# Sheet1.net
KiCad netlist of a schematic drawn in Altium Designer
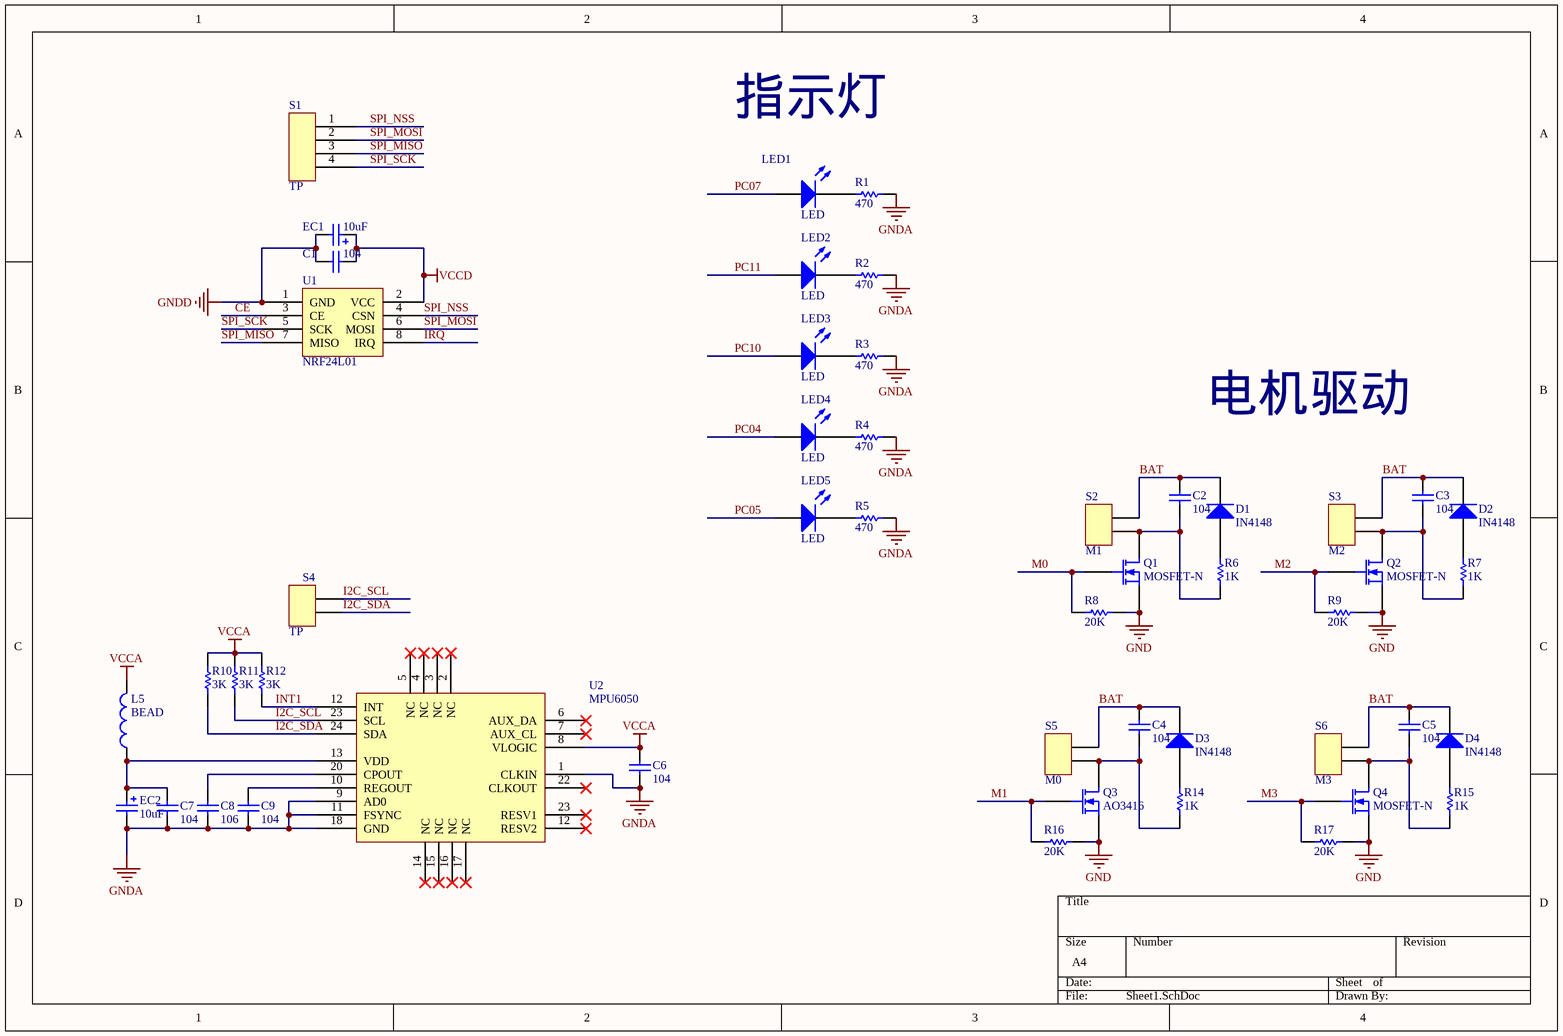
[diagram p0: Sheet1.SchDoc]

(export (version "E")
  (design (tool "Eeschema 10.0.6"))
  (components
    (comp (ref "C1") (value "104") (footprint "0603") (libsource (lib "yezi_sch") (part "CAP")))
    (comp (ref "C2") (value "104") (footprint "0603") (libsource (lib "yezi_sch") (part "CAP")))
    (comp (ref "C3") (value "104") (footprint "0603") (libsource (lib "yezi_sch") (part "CAP")))
    (comp (ref "C4") (value "104") (footprint "0603") (libsource (lib "yezi_sch") (part "CAP")))
    (comp (ref "C5") (value "104") (footprint "0603") (libsource (lib "yezi_sch") (part "CAP")))
    (comp (ref "C6") (value "104") (footprint "0603") (libsource (lib "yezi_sch") (part "CAP")))
    (comp (ref "C7") (value "104") (footprint "0603") (libsource (lib "yezi_sch") (part "CAP")))
    (comp (ref "C8") (value "106") (footprint "0805") (libsource (lib "yezi_sch") (part "CAP")))
    (comp (ref "C9") (value "104") (footprint "0603") (libsource (lib "yezi_sch") (part "CAP")))
    (comp (ref "D1") (value "IN4148") (footprint "1206") (libsource (lib "yezi_sch") (part "DIODE")))
    (comp (ref "D2") (value "IN4148") (footprint "1206") (libsource (lib "yezi_sch") (part "DIODE")))
    (comp (ref "D3") (value "IN4148") (footprint "1206") (libsource (lib "yezi_sch") (part "DIODE")))
    (comp (ref "D4") (value "IN4148") (footprint "1206") (libsource (lib "yezi_sch") (part "DIODE")))
    (comp (ref "EC1") (value "10uF") (footprint "1206") (libsource (lib "yezi_sch") (part "EC")))
    (comp (ref "EC2") (value "10uF") (footprint "1206") (libsource (lib "yezi_sch") (part "EC")))
    (comp (ref "L5")
      (value "BEAD")
      (footprint "0603")
      (description "Inductor")
      (fields (field (name "PUBLISHER") "Altium Limited"))
      (libsource (lib "yezi_sch") (part "Inductor"))
    )
    (comp (ref "LED1") (value "LED") (footprint "0805") (libsource (lib "yezi_sch") (part "LED")))
    (comp (ref "LED2") (value "LED") (footprint "0805") (libsource (lib "yezi_sch") (part "LED")))
    (comp (ref "LED3") (value "LED") (footprint "0805") (libsource (lib "yezi_sch") (part "LED")))
    (comp (ref "LED4") (value "LED") (footprint "0805") (libsource (lib "yezi_sch") (part "LED")))
    (comp (ref "LED5") (value "LED") (footprint "0805") (libsource (lib "yezi_sch") (part "LED")))
    (comp (ref "Q1")
      (value "MOSFET-N")
      (footprint "SOT-23_N")
      (description "N-Channel MOSFET")
      (fields (field (name "PUBLISHER") "Altium Limited"))
      (libsource (lib "yezi_sch") (part "MOSFET-N"))
    )
    (comp (ref "Q2")
      (value "MOSFET-N")
      (footprint "SOT-23_N")
      (description "N-Channel MOSFET")
      (fields (field (name "PUBLISHER") "Altium Limited"))
      (libsource (lib "yezi_sch") (part "MOSFET-N"))
    )
    (comp (ref "Q3")
      (value "AO3416")
      (footprint "SOT-23_N")
      (description "N-Channel MOSFET")
      (fields (field (name "PUBLISHER") "Altium Limited"))
      (libsource (lib "yezi_sch") (part "MOSFET-N"))
    )
    (comp (ref "Q4")
      (value "MOSFET-N")
      (footprint "SOT-23_N")
      (description "N-Channel MOSFET")
      (fields (field (name "PUBLISHER") "Altium Limited"))
      (libsource (lib "yezi_sch") (part "MOSFET-N"))
    )
    (comp (ref "R1") (value "470") (footprint "0603") (libsource (lib "yezi_sch") (part "RES")))
    (comp (ref "R2") (value "470") (footprint "0603") (libsource (lib "yezi_sch") (part "RES")))
    (comp (ref "R3") (value "470") (footprint "0603") (libsource (lib "yezi_sch") (part "RES")))
    (comp (ref "R4") (value "470") (footprint "0603") (libsource (lib "yezi_sch") (part "RES")))
    (comp (ref "R5") (value "470") (footprint "0603") (libsource (lib "yezi_sch") (part "RES")))
    (comp (ref "R6") (value "1K") (footprint "0603") (libsource (lib "yezi_sch") (part "RES")))
    (comp (ref "R7") (value "1K") (footprint "0603") (libsource (lib "yezi_sch") (part "RES")))
    (comp (ref "R8") (value "20K") (footprint "0603") (libsource (lib "yezi_sch") (part "RES")))
    (comp (ref "R9") (value "20K") (footprint "0603") (libsource (lib "yezi_sch") (part "RES")))
    (comp (ref "R10") (value "3K") (footprint "0603") (libsource (lib "yezi_sch") (part "RES")))
    (comp (ref "R11") (value "3K") (footprint "0603") (libsource (lib "yezi_sch") (part "RES")))
    (comp (ref "R12") (value "3K") (footprint "0603") (libsource (lib "yezi_sch") (part "RES")))
    (comp (ref "R14") (value "1K") (footprint "0603") (libsource (lib "yezi_sch") (part "RES")))
    (comp (ref "R15") (value "1K") (footprint "0603") (libsource (lib "yezi_sch") (part "RES")))
    (comp (ref "R16") (value "20K") (footprint "0603") (libsource (lib "yezi_sch") (part "RES")))
    (comp (ref "R17") (value "20K") (footprint "0603") (libsource (lib "yezi_sch") (part "RES")))
    (comp (ref "S1") (value "TP") (footprint "TP4") (libsource (lib "yezi_sch") (part "CON4")))
    (comp (ref "S2") (value "M1") (footprint "0805") (libsource (lib "yezi_sch") (part "CON2")))
    (comp (ref "S3") (value "M2") (footprint "0805") (libsource (lib "yezi_sch") (part "CON2")))
    (comp (ref "S4") (value "TP") (footprint "TP2") (libsource (lib "yezi_sch") (part "CON2")))
    (comp (ref "S5") (value "M0") (footprint "0805") (libsource (lib "yezi_sch") (part "CON2")))
    (comp (ref "S6") (value "M3") (footprint "0805") (libsource (lib "yezi_sch") (part "CON2")))
    (comp (ref "U1") (value "NRF24L01") (footprint "CN8") (libsource (lib "yezi_sch") (part "NRF24L01")))
    (comp (ref "U2")
      (value "MPU6050")
      (footprint "QFN50P400X400X95_HS-25N")
      (libsource (lib "yezi_sch") (part "MPU6050"))
    )
  )
  (nets
    (net (code "1") (name "/BAT") (class "Default")
      (node (ref "C2") (pin "2") (pinfunction "2_2") (pintype "passive"))
      (node (ref "C3") (pin "2") (pinfunction "2_2") (pintype "passive"))
      (node (ref "C4") (pin "2") (pinfunction "2_2") (pintype "passive"))
      (node (ref "C5") (pin "2") (pinfunction "2_2") (pintype "passive"))
      (node (ref "D1") (pin "2") (pinfunction "K_2") (pintype "passive"))
      (node (ref "D2") (pin "2") (pinfunction "K_2") (pintype "passive"))
      (node (ref "D3") (pin "2") (pinfunction "K_2") (pintype "passive"))
      (node (ref "D4") (pin "2") (pinfunction "K_2") (pintype "passive"))
      (node (ref "S2") (pin "1") (pinfunction "1_1") (pintype "passive"))
      (node (ref "S3") (pin "1") (pinfunction "1_1") (pintype "passive"))
      (node (ref "S5") (pin "1") (pinfunction "1_1") (pintype "passive"))
      (node (ref "S6") (pin "1") (pinfunction "1_1") (pintype "passive"))
    )
    (net (code "2") (name "/CE") (class "Default")
      (node (ref "U1") (pin "3") (pinfunction "CE_3") (pintype "passive"))
    )
    (net (code "3") (name "/I2C_SCL") (class "Default")
      (node (ref "R11") (pin "1") (pinfunction "1_1") (pintype "passive"))
      (node (ref "S4") (pin "1") (pinfunction "1_1") (pintype "passive"))
      (node (ref "U2") (pin "23") (pinfunction "SCL_23") (pintype "passive"))
    )
    (net (code "4") (name "/I2C_SDA") (class "Default")
      (node (ref "R10") (pin "1") (pinfunction "1_1") (pintype "passive"))
      (node (ref "S4") (pin "2") (pinfunction "2_2") (pintype "passive"))
      (node (ref "U2") (pin "24") (pinfunction "SDA_24") (pintype "passive"))
    )
    (net (code "5") (name "/INT1") (class "Default")
      (node (ref "R12") (pin "1") (pinfunction "1_1") (pintype "passive"))
      (node (ref "U2") (pin "12") (pinfunction "INT_12") (pintype "passive"))
    )
    (net (code "6") (name "/IRQ") (class "Default")
      (node (ref "U1") (pin "8") (pinfunction "IRQ_8") (pintype "passive"))
    )
    (net (code "7") (name "/M0") (class "Default")
      (node (ref "Q1") (pin "2") (pinfunction "G_2") (pintype "passive"))
      (node (ref "R8") (pin "1") (pinfunction "1_1") (pintype "passive"))
    )
    (net (code "8") (name "/M1") (class "Default")
      (node (ref "Q3") (pin "2") (pinfunction "G_2") (pintype "passive"))
      (node (ref "R16") (pin "1") (pinfunction "1_1") (pintype "passive"))
    )
    (net (code "9") (name "/M2") (class "Default")
      (node (ref "Q2") (pin "2") (pinfunction "G_2") (pintype "passive"))
      (node (ref "R9") (pin "1") (pinfunction "1_1") (pintype "passive"))
    )
    (net (code "10") (name "/M3") (class "Default")
      (node (ref "Q4") (pin "2") (pinfunction "G_2") (pintype "passive"))
      (node (ref "R17") (pin "1") (pinfunction "1_1") (pintype "passive"))
    )
    (net (code "11") (name "/PC04") (class "Default")
      (node (ref "LED4") (pin "1") (pinfunction "A_1") (pintype "passive"))
    )
    (net (code "12") (name "/PC05") (class "Default")
      (node (ref "LED5") (pin "1") (pinfunction "A_1") (pintype "passive"))
    )
    (net (code "13") (name "/PC07") (class "Default")
      (node (ref "LED1") (pin "1") (pinfunction "A_1") (pintype "passive"))
    )
    (net (code "14") (name "/PC10") (class "Default")
      (node (ref "LED3") (pin "1") (pinfunction "A_1") (pintype "passive"))
    )
    (net (code "15") (name "/PC11") (class "Default")
      (node (ref "LED2") (pin "1") (pinfunction "A_1") (pintype "passive"))
    )
    (net (code "16") (name "/SPI_MISO") (class "Default")
      (node (ref "S1") (pin "3") (pinfunction "3_3") (pintype "passive"))
      (node (ref "U1") (pin "7") (pinfunction "MISO_7") (pintype "passive"))
    )
    (net (code "17") (name "/SPI_MOSI") (class "Default")
      (node (ref "S1") (pin "2") (pinfunction "2_2") (pintype "passive"))
      (node (ref "U1") (pin "6") (pinfunction "MOSI_6") (pintype "passive"))
    )
    (net (code "18") (name "/SPI_NSS") (class "Default")
      (node (ref "S1") (pin "1") (pinfunction "1_1") (pintype "passive"))
      (node (ref "U1") (pin "4") (pinfunction "CSN_4") (pintype "passive"))
    )
    (net (code "19") (name "/SPI_SCK") (class "Default")
      (node (ref "S1") (pin "4") (pinfunction "4_4") (pintype "passive"))
      (node (ref "U1") (pin "5") (pinfunction "SCK_5") (pintype "passive"))
    )
    (net (code "20") (name "GND") (class "Default")
      (node (ref "Q1") (pin "3") (pinfunction "S_3") (pintype "passive"))
      (node (ref "Q2") (pin "3") (pinfunction "S_3") (pintype "passive"))
      (node (ref "Q3") (pin "3") (pinfunction "S_3") (pintype "passive"))
      (node (ref "Q4") (pin "3") (pinfunction "S_3") (pintype "passive"))
      (node (ref "R16") (pin "2") (pinfunction "2_2") (pintype "passive"))
      (node (ref "R17") (pin "2") (pinfunction "2_2") (pintype "passive"))
      (node (ref "R8") (pin "2") (pinfunction "2_2") (pintype "passive"))
      (node (ref "R9") (pin "2") (pinfunction "2_2") (pintype "passive"))
    )
    (net (code "21") (name "GNDA") (class "Default")
      (node (ref "C6") (pin "2") (pinfunction "2_2") (pintype "passive"))
      (node (ref "C7") (pin "1") (pinfunction "1_1") (pintype "passive"))
      (node (ref "C8") (pin "2") (pinfunction "2_2") (pintype "passive"))
      (node (ref "C9") (pin "2") (pinfunction "2_2") (pintype "passive"))
      (node (ref "EC2") (pin "2") (pinfunction "2_2") (pintype "passive"))
      (node (ref "R1") (pin "2") (pinfunction "2_2") (pintype "passive"))
      (node (ref "R2") (pin "2") (pinfunction "2_2") (pintype "passive"))
      (node (ref "R3") (pin "2") (pinfunction "2_2") (pintype "passive"))
      (node (ref "R4") (pin "2") (pinfunction "2_2") (pintype "passive"))
      (node (ref "R5") (pin "2") (pinfunction "2_2") (pintype "passive"))
      (node (ref "U2") (pin "1") (pinfunction "CLKIN_1") (pintype "passive"))
      (node (ref "U2") (pin "11") (pinfunction "FSYNC_11") (pintype "passive"))
      (node (ref "U2") (pin "18") (pinfunction "GND_18") (pintype "passive"))
      (node (ref "U2") (pin "9") (pinfunction "AD0_9") (pintype "passive"))
    )
    (net (code "22") (name "GNDD") (class "Default")
      (node (ref "C1") (pin "1") (pinfunction "1_1") (pintype "passive"))
      (node (ref "EC1") (pin "2") (pinfunction "2_2") (pintype "passive"))
      (node (ref "U1") (pin "1") (pinfunction "GND_1") (pintype "passive"))
    )
    (net (code "23") (name "Net-(D1-A)") (class "Default")
      (node (ref "D1") (pin "1") (pinfunction "A_1") (pintype "passive"))
      (node (ref "R6") (pin "2") (pinfunction "2_2") (pintype "passive"))
    )
    (net (code "24") (name "Net-(D2-A)") (class "Default")
      (node (ref "D2") (pin "1") (pinfunction "A_1") (pintype "passive"))
      (node (ref "R7") (pin "2") (pinfunction "2_2") (pintype "passive"))
    )
    (net (code "25") (name "Net-(D3-A)") (class "Default")
      (node (ref "D3") (pin "1") (pinfunction "A_1") (pintype "passive"))
      (node (ref "R14") (pin "2") (pinfunction "2_2") (pintype "passive"))
    )
    (net (code "26") (name "Net-(D4-A)") (class "Default")
      (node (ref "D4") (pin "1") (pinfunction "A_1") (pintype "passive"))
      (node (ref "R15") (pin "2") (pinfunction "2_2") (pintype "passive"))
    )
    (net (code "27") (name "Net-(LED1-K)") (class "Default")
      (node (ref "LED1") (pin "2") (pinfunction "K_2") (pintype "passive"))
      (node (ref "R1") (pin "1") (pinfunction "1_1") (pintype "passive"))
    )
    (net (code "28") (name "Net-(LED2-K)") (class "Default")
      (node (ref "LED2") (pin "2") (pinfunction "K_2") (pintype "passive"))
      (node (ref "R2") (pin "1") (pinfunction "1_1") (pintype "passive"))
    )
    (net (code "29") (name "Net-(LED3-K)") (class "Default")
      (node (ref "LED3") (pin "2") (pinfunction "K_2") (pintype "passive"))
      (node (ref "R3") (pin "1") (pinfunction "1_1") (pintype "passive"))
    )
    (net (code "30") (name "Net-(LED4-K)") (class "Default")
      (node (ref "LED4") (pin "2") (pinfunction "K_2") (pintype "passive"))
      (node (ref "R4") (pin "1") (pinfunction "1_1") (pintype "passive"))
    )
    (net (code "31") (name "Net-(LED5-K)") (class "Default")
      (node (ref "LED5") (pin "2") (pinfunction "K_2") (pintype "passive"))
      (node (ref "R5") (pin "1") (pinfunction "1_1") (pintype "passive"))
    )
    (net (code "32") (name "Net-(Q1-D)") (class "Default")
      (node (ref "C2") (pin "1") (pinfunction "1_1") (pintype "passive"))
      (node (ref "Q1") (pin "1") (pinfunction "D_1") (pintype "passive"))
      (node (ref "R6") (pin "1") (pinfunction "1_1") (pintype "passive"))
      (node (ref "S2") (pin "2") (pinfunction "2_2") (pintype "passive"))
    )
    (net (code "33") (name "Net-(Q2-D)") (class "Default")
      (node (ref "C3") (pin "1") (pinfunction "1_1") (pintype "passive"))
      (node (ref "Q2") (pin "1") (pinfunction "D_1") (pintype "passive"))
      (node (ref "R7") (pin "1") (pinfunction "1_1") (pintype "passive"))
      (node (ref "S3") (pin "2") (pinfunction "2_2") (pintype "passive"))
    )
    (net (code "34") (name "Net-(Q3-D)") (class "Default")
      (node (ref "C4") (pin "1") (pinfunction "1_1") (pintype "passive"))
      (node (ref "Q3") (pin "1") (pinfunction "D_1") (pintype "passive"))
      (node (ref "R14") (pin "1") (pinfunction "1_1") (pintype "passive"))
      (node (ref "S5") (pin "2") (pinfunction "2_2") (pintype "passive"))
    )
    (net (code "35") (name "Net-(Q4-D)") (class "Default")
      (node (ref "C5") (pin "1") (pinfunction "1_1") (pintype "passive"))
      (node (ref "Q4") (pin "1") (pinfunction "D_1") (pintype "passive"))
      (node (ref "R15") (pin "1") (pinfunction "1_1") (pintype "passive"))
      (node (ref "S6") (pin "2") (pinfunction "2_2") (pintype "passive"))
    )
    (net (code "36") (name "Net-(U2-CPOUT)") (class "Default")
      (node (ref "C8") (pin "1") (pinfunction "1_1") (pintype "passive"))
      (node (ref "U2") (pin "20") (pinfunction "CPOUT_20") (pintype "passive"))
    )
    (net (code "37") (name "Net-(U2-REGOUT)") (class "Default")
      (node (ref "C9") (pin "1") (pinfunction "1_1") (pintype "passive"))
      (node (ref "U2") (pin "10") (pinfunction "REGOUT_10") (pintype "passive"))
    )
    (net (code "38") (name "Net-(U2-VDD)") (class "Default")
      (node (ref "C7") (pin "2") (pinfunction "2_2") (pintype "passive"))
      (node (ref "EC2") (pin "1") (pinfunction "1_1") (pintype "passive"))
      (node (ref "L5") (pin "1") (pinfunction "1_1") (pintype "passive"))
      (node (ref "U2") (pin "13") (pinfunction "VDD_13") (pintype "passive"))
    )
    (net (code "39") (name "VCCA") (class "Default")
      (node (ref "C6") (pin "1") (pinfunction "1_1") (pintype "passive"))
      (node (ref "L5") (pin "2") (pinfunction "2_2") (pintype "passive"))
      (node (ref "R10") (pin "2") (pinfunction "2_2") (pintype "passive"))
      (node (ref "R11") (pin "2") (pinfunction "2_2") (pintype "passive"))
      (node (ref "R12") (pin "2") (pinfunction "2_2") (pintype "passive"))
      (node (ref "U2") (pin "8") (pinfunction "VLOGIC_8") (pintype "passive"))
    )
    (net (code "40") (name "VCCD") (class "Default")
      (node (ref "C1") (pin "2") (pinfunction "2_2") (pintype "passive"))
      (node (ref "EC1") (pin "1") (pinfunction "1_1") (pintype "passive"))
      (node (ref "U1") (pin "2") (pinfunction "VCC_2") (pintype "passive"))
    )
    (net (code "41") (name "unconnected-(U2-AUX_CL-Pad7)") (class "Default")
      (node (ref "U2") (pin "7") (pinfunction "AUX_CL_7") (pintype "passive+no_connect"))
    )
    (net (code "42") (name "unconnected-(U2-AUX_DA-Pad6)") (class "Default")
      (node (ref "U2") (pin "6") (pinfunction "AUX_DA_6") (pintype "passive+no_connect"))
    )
    (net (code "43") (name "unconnected-(U2-CLKOUT-Pad22)") (class "Default")
      (node (ref "U2") (pin "22") (pinfunction "CLKOUT_22") (pintype "passive+no_connect"))
    )
    (net (code "44") (name "unconnected-(U2-NC-Pad2)") (class "Default")
      (node (ref "U2") (pin "2") (pinfunction "NC_2") (pintype "passive+no_connect"))
    )
    (net (code "45") (name "unconnected-(U2-NC-Pad3)") (class "Default")
      (node (ref "U2") (pin "3") (pinfunction "NC_3") (pintype "passive+no_connect"))
    )
    (net (code "46") (name "unconnected-(U2-NC-Pad4)") (class "Default")
      (node (ref "U2") (pin "4") (pinfunction "NC_4") (pintype "passive+no_connect"))
    )
    (net (code "47") (name "unconnected-(U2-NC-Pad5)") (class "Default")
      (node (ref "U2") (pin "5") (pinfunction "NC_5") (pintype "passive+no_connect"))
    )
    (net (code "48") (name "unconnected-(U2-NC-Pad14)") (class "Default")
      (node (ref "U2") (pin "14") (pinfunction "NC_14") (pintype "passive+no_connect"))
    )
    (net (code "49") (name "unconnected-(U2-NC-Pad15)") (class "Default")
      (node (ref "U2") (pin "15") (pinfunction "NC_15") (pintype "passive+no_connect"))
    )
    (net (code "50") (name "unconnected-(U2-NC-Pad16)") (class "Default")
      (node (ref "U2") (pin "16") (pinfunction "NC_16") (pintype "passive+no_connect"))
    )
    (net (code "51") (name "unconnected-(U2-NC-Pad17)") (class "Default")
      (node (ref "U2") (pin "17") (pinfunction "NC_17") (pintype "passive+no_connect"))
    )
    (net (code "52") (name "unconnected-(U2-RESV1-Pad23)") (class "Default")
      (node (ref "U2") (pin "23") (pinfunction "RESV1_23") (pintype "passive+no_connect"))
    )
    (net (code "53") (name "unconnected-(U2-RESV2-Pad12)") (class "Default")
      (node (ref "U2") (pin "12") (pinfunction "RESV2_12") (pintype "passive+no_connect"))
    )
  )
)
